# arduino.net
KiCad netlist of a schematic drawn in EAGLE
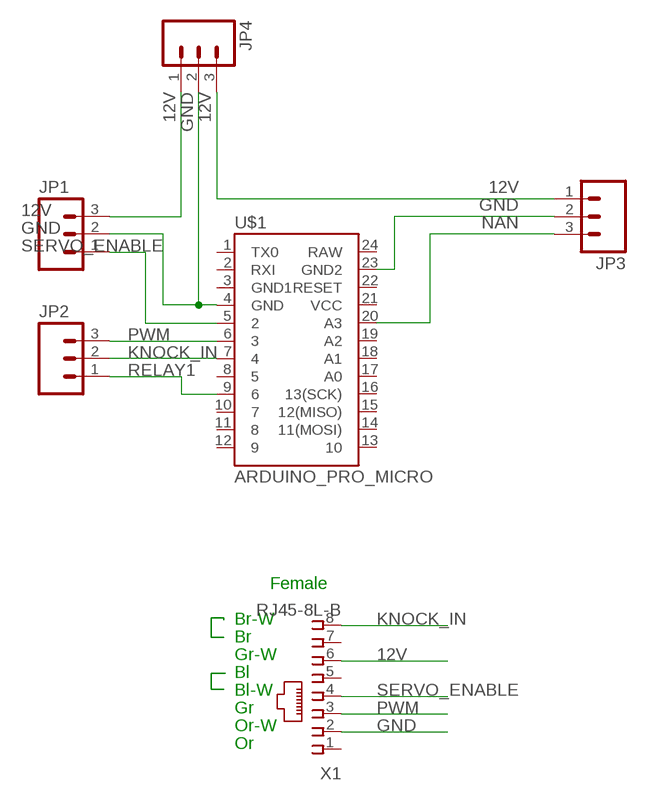
[diagram p0: schematic, sheet 1]

(export (version "E")
  (design (tool "Eeschema 10.0.6"))
  (components
    (comp (ref "JP1")
      (value "M03")
      (footprint "eagle-import:JST-3-SMD")
      (libsource (lib "eagle-import") (part "M03"))
    )
    (comp (ref "JP2")
      (value "M03")
      (footprint "eagle-import:JST-3-SMD")
      (libsource (lib "eagle-import") (part "M03"))
    )
    (comp (ref "JP3")
      (value "M03")
      (footprint "eagle-import:JST-3-SMD")
      (libsource (lib "eagle-import") (part "M03"))
    )
    (comp (ref "JP4")
      (value "M03")
      (footprint "eagle-import:JST-3-SMD")
      (libsource (lib "eagle-import") (part "M03"))
    )
    (comp (ref "U$1")
      (value "ARDUINO_PRO_MICRO")
      (footprint "eagle-import:ARDUINO_PRO_MICRO")
      (libsource (lib "eagle-import") (part "ARDUINO_PRO_MICRO"))
    )
    (comp (ref "X1")
      (value "RJ45-8L-B")
      (footprint "eagle-import:RJ45-NO-SHIELD")
      (fields (field (name "MF") "TYCO ELECTRONICS"))
      (libsource (lib "eagle-import") (part "RJ45-8L-B"))
    )
  )
  (nets
    (net (code "1") (name "/12V") (class "Default")
      (node (ref "JP1") (pin "3") (pinfunction "3_3") (pintype "passive"))
      (node (ref "JP3") (pin "1") (pinfunction "1_1") (pintype "passive"))
      (node (ref "JP4") (pin "1") (pinfunction "1_1") (pintype "passive"))
      (node (ref "JP4") (pin "3") (pinfunction "3_3") (pintype "passive"))
      (node (ref "X1") (pin "6") (pinfunction "6_6") (pintype "passive"))
    )
    (net (code "2") (name "/GND") (class "Default")
      (node (ref "JP1") (pin "2") (pinfunction "2_2") (pintype "passive"))
      (node (ref "JP3") (pin "2") (pinfunction "2_2") (pintype "passive"))
      (node (ref "JP4") (pin "2") (pinfunction "2_2") (pintype "passive"))
      (node (ref "U$1") (pin "23") (pinfunction "GND2_23") (pintype "bidirectional"))
      (node (ref "U$1") (pin "4") (pinfunction "GND_4") (pintype "bidirectional"))
      (node (ref "X1") (pin "2") (pinfunction "2_2") (pintype "passive"))
    )
    (net (code "3") (name "/KNOCK_IN") (class "Default")
      (node (ref "JP2") (pin "2") (pinfunction "2_2") (pintype "passive"))
      (node (ref "U$1") (pin "7") (pinfunction "4_7") (pintype "bidirectional"))
      (node (ref "X1") (pin "8") (pinfunction "8_8") (pintype "passive"))
    )
    (net (code "4") (name "/NAN") (class "Default")
      (node (ref "JP3") (pin "3") (pinfunction "3_3") (pintype "passive"))
      (node (ref "U$1") (pin "20") (pinfunction "A3_20") (pintype "bidirectional"))
    )
    (net (code "5") (name "/PWM") (class "Default")
      (node (ref "JP2") (pin "3") (pinfunction "3_3") (pintype "passive"))
      (node (ref "U$1") (pin "6") (pinfunction "3_6") (pintype "bidirectional"))
      (node (ref "X1") (pin "3") (pinfunction "3_3") (pintype "passive"))
    )
    (net (code "6") (name "/RELAY1") (class "Default")
      (node (ref "JP2") (pin "1") (pinfunction "1_1") (pintype "passive"))
      (node (ref "U$1") (pin "9") (pinfunction "6_9") (pintype "bidirectional"))
    )
    (net (code "7") (name "/SERVO_ENABLE") (class "Default")
      (node (ref "JP1") (pin "1") (pinfunction "1_1") (pintype "passive"))
      (node (ref "U$1") (pin "5") (pinfunction "2_5") (pintype "bidirectional"))
      (node (ref "X1") (pin "4") (pinfunction "4_4") (pintype "passive"))
    )
    (net (code "8") (name "unconnected-(U$1-5-Pad8)") (class "Default")
      (node (ref "U$1") (pin "8") (pinfunction "5_8") (pintype "bidirectional"))
    )
    (net (code "9") (name "unconnected-(U$1-7-Pad10)") (class "Default")
      (node (ref "U$1") (pin "10") (pinfunction "7_10") (pintype "bidirectional"))
    )
    (net (code "10") (name "unconnected-(U$1-8-Pad11)") (class "Default")
      (node (ref "U$1") (pin "11") (pinfunction "8_11") (pintype "bidirectional"))
    )
    (net (code "11") (name "unconnected-(U$1-9-Pad12)") (class "Default")
      (node (ref "U$1") (pin "12") (pinfunction "9_12") (pintype "bidirectional"))
    )
    (net (code "12") (name "unconnected-(U$1-10-Pad13)") (class "Default")
      (node (ref "U$1") (pin "13") (pinfunction "10_13") (pintype "bidirectional"))
    )
    (net (code "13") (name "unconnected-(U$1-11(MOSI)-Pad14)") (class "Default")
      (node (ref "U$1") (pin "14") (pinfunction "11(MOSI)_14") (pintype "bidirectional"))
    )
    (net (code "14") (name "unconnected-(U$1-12(MISO)-Pad15)") (class "Default")
      (node (ref "U$1") (pin "15") (pinfunction "12(MISO)_15") (pintype "bidirectional"))
    )
    (net (code "15") (name "unconnected-(U$1-13(SCK)-Pad16)") (class "Default")
      (node (ref "U$1") (pin "16") (pinfunction "13(SCK)_16") (pintype "bidirectional"))
    )
    (net (code "16") (name "unconnected-(U$1-A0-Pad17)") (class "Default")
      (node (ref "U$1") (pin "17") (pinfunction "A0_17") (pintype "bidirectional"))
    )
    (net (code "17") (name "unconnected-(U$1-A1-Pad18)") (class "Default")
      (node (ref "U$1") (pin "18") (pinfunction "A1_18") (pintype "bidirectional"))
    )
    (net (code "18") (name "unconnected-(U$1-A2-Pad19)") (class "Default")
      (node (ref "U$1") (pin "19") (pinfunction "A2_19") (pintype "bidirectional"))
    )
    (net (code "19") (name "unconnected-(U$1-GND1-Pad3)") (class "Default")
      (node (ref "U$1") (pin "3") (pinfunction "GND1_3") (pintype "bidirectional"))
    )
    (net (code "20") (name "unconnected-(U$1-RAW-Pad24)") (class "Default")
      (node (ref "U$1") (pin "24") (pinfunction "RAW_24") (pintype "bidirectional"))
    )
    (net (code "21") (name "unconnected-(U$1-RESET-Pad22)") (class "Default")
      (node (ref "U$1") (pin "22") (pinfunction "RESET_22") (pintype "bidirectional"))
    )
    (net (code "22") (name "unconnected-(U$1-RXI-Pad2)") (class "Default")
      (node (ref "U$1") (pin "2") (pinfunction "RXI_2") (pintype "bidirectional"))
    )
    (net (code "23") (name "unconnected-(U$1-TX0-Pad1)") (class "Default")
      (node (ref "U$1") (pin "1") (pinfunction "TX0_1") (pintype "bidirectional"))
    )
    (net (code "24") (name "unconnected-(U$1-VCC-Pad21)") (class "Default")
      (node (ref "U$1") (pin "21") (pinfunction "VCC_21") (pintype "bidirectional"))
    )
    (net (code "25") (name "unconnected-(X1-Pad1)") (class "Default")
      (node (ref "X1") (pin "1") (pinfunction "1_1") (pintype "passive"))
    )
    (net (code "26") (name "unconnected-(X1-Pad5)") (class "Default")
      (node (ref "X1") (pin "5") (pinfunction "5_5") (pintype "passive"))
    )
    (net (code "27") (name "unconnected-(X1-Pad7)") (class "Default")
      (node (ref "X1") (pin "7") (pinfunction "7_7") (pintype "passive"))
    )
  )
)
